# Sensor_Suite.net
KiCad netlist of a schematic drawn in Altium Designer
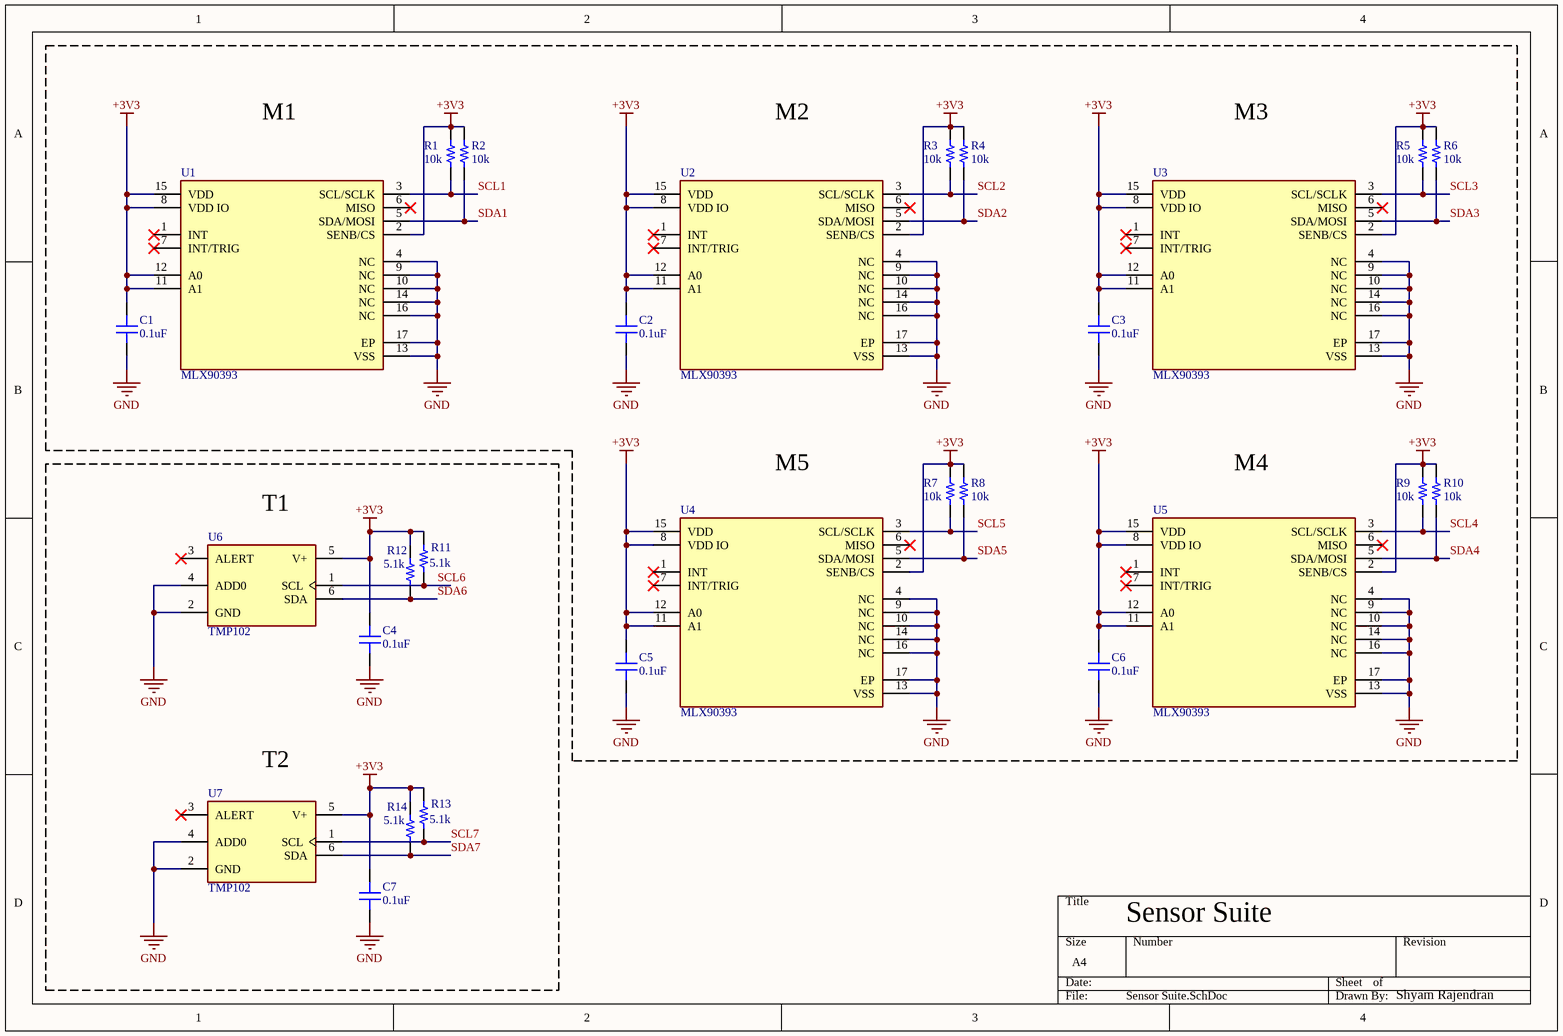
[diagram p0: Sensor Suite.SchDoc]

(export (version "E")
  (design (tool "Eeschema 10.0.6"))
  (components
    (comp (ref "C1")
      (value "10uF")
      (footprint "CAP 0603_1608")
      (description "0603")
      (fields
        (field (name "PART NUMBER") "GCJ188C70J335KE02D")
        (field (name "CAPACITANCE") "0.1uF")
        (field (name "MANUFACTURER") "Murata Electronics")
      )
      (libsource (lib "Celestial Altium Library - altium_library") (part "Capacitor"))
    )
    (comp (ref "C2")
      (value "10uF")
      (footprint "CAP 0603_1608")
      (description "0603")
      (fields
        (field (name "PART NUMBER") "GCJ188C70J335KE02D")
        (field (name "CAPACITANCE") "0.1uF")
        (field (name "MANUFACTURER") "Murata Electronics")
      )
      (libsource (lib "Celestial Altium Library - altium_library") (part "Capacitor"))
    )
    (comp (ref "C3")
      (value "10uF")
      (footprint "CAP 0603_1608")
      (description "0603")
      (fields
        (field (name "PART NUMBER") "GCJ188C70J335KE02D")
        (field (name "CAPACITANCE") "0.1uF")
        (field (name "MANUFACTURER") "Murata Electronics")
      )
      (libsource (lib "Celestial Altium Library - altium_library") (part "Capacitor"))
    )
    (comp (ref "C4")
      (value "10uF")
      (footprint "CAP 0603_1608")
      (description "0603")
      (fields
        (field (name "PART NUMBER") "GCJ188C70J335KE02D")
        (field (name "CAPACITANCE") "0.1uF")
        (field (name "MANUFACTURER") "Murata Electronics")
      )
      (libsource (lib "Celestial Altium Library - altium_library") (part "Capacitor"))
    )
    (comp (ref "C5")
      (value "10uF")
      (footprint "CAP 0603_1608")
      (description "0603")
      (fields
        (field (name "PART NUMBER") "GCJ188C70J335KE02D")
        (field (name "CAPACITANCE") "0.1uF")
        (field (name "MANUFACTURER") "Murata Electronics")
      )
      (libsource (lib "Celestial Altium Library - altium_library") (part "Capacitor"))
    )
    (comp (ref "C6")
      (value "10uF")
      (footprint "CAP 0603_1608")
      (description "0603")
      (fields
        (field (name "PART NUMBER") "GCJ188C70J335KE02D")
        (field (name "CAPACITANCE") "0.1uF")
        (field (name "MANUFACTURER") "Murata Electronics")
      )
      (libsource (lib "Celestial Altium Library - altium_library") (part "Capacitor"))
    )
    (comp (ref "C7")
      (value "10uF")
      (footprint "CAP 0603_1608")
      (description "0603")
      (fields
        (field (name "PART NUMBER") "GCJ188C70J335KE02D")
        (field (name "CAPACITANCE") "0.1uF")
        (field (name "MANUFACTURER") "Murata Electronics")
      )
      (libsource (lib "Celestial Altium Library - altium_library") (part "Capacitor"))
    )
    (comp (ref "R1")
      (value "10k")
      (footprint "RES 0603_1608")
      (description "RES 10K OHM 0.1% 1/16W 0603")
      (fields
        (field (name "PART NUMBER") "RNCS0603BKE10K0")
        (field (name "MANUFACTURER") "Stackpole Electronics Inc")
      )
      (libsource (lib "Celestial Altium Library - altium_library") (part "Resistor"))
    )
    (comp (ref "R2")
      (value "10k")
      (footprint "RES 0603_1608")
      (description "RES 10K OHM 0.1% 1/16W 0603")
      (fields
        (field (name "PART NUMBER") "RNCS0603BKE10K0")
        (field (name "MANUFACTURER") "Stackpole Electronics Inc")
      )
      (libsource (lib "Celestial Altium Library - altium_library") (part "Resistor"))
    )
    (comp (ref "R3")
      (value "10k")
      (footprint "RES 0603_1608")
      (description "RES 10K OHM 0.1% 1/16W 0603")
      (fields
        (field (name "PART NUMBER") "RNCS0603BKE10K0")
        (field (name "MANUFACTURER") "Stackpole Electronics Inc")
      )
      (libsource (lib "Celestial Altium Library - altium_library") (part "Resistor"))
    )
    (comp (ref "R4")
      (value "10k")
      (footprint "RES 0603_1608")
      (description "RES 10K OHM 0.1% 1/16W 0603")
      (fields
        (field (name "PART NUMBER") "RNCS0603BKE10K0")
        (field (name "MANUFACTURER") "Stackpole Electronics Inc")
      )
      (libsource (lib "Celestial Altium Library - altium_library") (part "Resistor"))
    )
    (comp (ref "R5")
      (value "10k")
      (footprint "RES 0603_1608")
      (description "RES 10K OHM 0.1% 1/16W 0603")
      (fields
        (field (name "PART NUMBER") "RNCS0603BKE10K0")
        (field (name "MANUFACTURER") "Stackpole Electronics Inc")
      )
      (libsource (lib "Celestial Altium Library - altium_library") (part "Resistor"))
    )
    (comp (ref "R6")
      (value "10k")
      (footprint "RES 0603_1608")
      (description "RES 10K OHM 0.1% 1/16W 0603")
      (fields
        (field (name "PART NUMBER") "RNCS0603BKE10K0")
        (field (name "MANUFACTURER") "Stackpole Electronics Inc")
      )
      (libsource (lib "Celestial Altium Library - altium_library") (part "Resistor"))
    )
    (comp (ref "R7")
      (value "10k")
      (footprint "RES 0603_1608")
      (description "RES 10K OHM 0.1% 1/16W 0603")
      (fields
        (field (name "PART NUMBER") "RNCS0603BKE10K0")
        (field (name "MANUFACTURER") "Stackpole Electronics Inc")
      )
      (libsource (lib "Celestial Altium Library - altium_library") (part "Resistor"))
    )
    (comp (ref "R8")
      (value "10k")
      (footprint "RES 0603_1608")
      (description "RES 10K OHM 0.1% 1/16W 0603")
      (fields
        (field (name "PART NUMBER") "RNCS0603BKE10K0")
        (field (name "MANUFACTURER") "Stackpole Electronics Inc")
      )
      (libsource (lib "Celestial Altium Library - altium_library") (part "Resistor"))
    )
    (comp (ref "R9")
      (value "10k")
      (footprint "RES 0603_1608")
      (description "RES 10K OHM 0.1% 1/16W 0603")
      (fields
        (field (name "PART NUMBER") "RNCS0603BKE10K0")
        (field (name "MANUFACTURER") "Stackpole Electronics Inc")
      )
      (libsource (lib "Celestial Altium Library - altium_library") (part "Resistor"))
    )
    (comp (ref "R10")
      (value "10k")
      (footprint "RES 0603_1608")
      (description "RES 10K OHM 0.1% 1/16W 0603")
      (fields
        (field (name "PART NUMBER") "RNCS0603BKE10K0")
        (field (name "MANUFACTURER") "Stackpole Electronics Inc")
      )
      (libsource (lib "Celestial Altium Library - altium_library") (part "Resistor"))
    )
    (comp (ref "R11")
      (value "5.1k")
      (footprint "RES 0603_1608")
      (description "0603")
      (fields
        (field (name "PART NUMBER") "RNCS0603BKE10K0")
        (field (name "MANUFACTURER") "Stackpole Electronics Inc")
      )
      (libsource (lib "Celestial Altium Library - altium_library") (part "Resistor"))
    )
    (comp (ref "R12")
      (value "5.1k")
      (footprint "RES 0603_1608")
      (description "0603")
      (fields
        (field (name "PART NUMBER") "RNCS0603BKE10K0")
        (field (name "MANUFACTURER") "Stackpole Electronics Inc")
      )
      (libsource (lib "Celestial Altium Library - altium_library") (part "Resistor"))
    )
    (comp (ref "R13")
      (value "5.1k")
      (footprint "RES 0603_1608")
      (description "0603")
      (fields
        (field (name "PART NUMBER") "RNCS0603BKE10K0")
        (field (name "MANUFACTURER") "Stackpole Electronics Inc")
      )
      (libsource (lib "Celestial Altium Library - altium_library") (part "Resistor"))
    )
    (comp (ref "R14")
      (value "5.1k")
      (footprint "RES 0603_1608")
      (description "0603")
      (fields
        (field (name "PART NUMBER") "RNCS0603BKE10K0")
        (field (name "MANUFACTURER") "Stackpole Electronics Inc")
      )
      (libsource (lib "Celestial Altium Library - altium_library") (part "Resistor"))
    )
    (comp (ref "U1")
      (value "MLX90393")
      (footprint "MLX90393")
      (description "Analog Circuit, 1 Func")
      (fields
        (field (name "MANUFACTURER") "Melexis")
        (field (name "MANUFACTURER PART NUMBER") "MLX90393ELW-ABA-011-RE")
      )
      (libsource (lib "Schlib1") (part "MLX90393ELW-ABA-011-RE"))
    )
    (comp (ref "U2")
      (value "MLX90393")
      (footprint "MLX90393")
      (description "Analog Circuit, 1 Func")
      (fields
        (field (name "MANUFACTURER") "Melexis")
        (field (name "MANUFACTURER PART NUMBER") "MLX90393ELW-ABA-011-RE")
      )
      (libsource (lib "Schlib1") (part "MLX90393ELW-ABA-011-RE"))
    )
    (comp (ref "U3")
      (value "MLX90393")
      (footprint "MLX90393")
      (description "Analog Circuit, 1 Func")
      (fields
        (field (name "MANUFACTURER") "Melexis")
        (field (name "MANUFACTURER PART NUMBER") "MLX90393ELW-ABA-011-RE")
      )
      (libsource (lib "Schlib1") (part "MLX90393ELW-ABA-011-RE"))
    )
    (comp (ref "U4")
      (value "MLX90393")
      (footprint "MLX90393")
      (description "Analog Circuit, 1 Func")
      (fields
        (field (name "MANUFACTURER") "Melexis")
        (field (name "MANUFACTURER PART NUMBER") "MLX90393ELW-ABA-011-RE")
      )
      (libsource (lib "Schlib1") (part "MLX90393ELW-ABA-011-RE"))
    )
    (comp (ref "U5")
      (value "MLX90393")
      (footprint "MLX90393")
      (description "Analog Circuit, 1 Func")
      (fields
        (field (name "MANUFACTURER") "Melexis")
        (field (name "MANUFACTURER PART NUMBER") "MLX90393ELW-ABA-011-RE")
      )
      (libsource (lib "Schlib1") (part "MLX90393ELW-ABA-011-RE"))
    )
    (comp (ref "U6")
      (value "TMP102")
      (footprint "TMP102")
      (description "SENSOR DIGITAL -40C-125C SOT563")
      (libsource (lib "Schlib1") (part "TMP102"))
    )
    (comp (ref "U7")
      (value "TMP102")
      (footprint "TMP102")
      (description "SENSOR DIGITAL -40C-125C SOT563")
      (libsource (lib "Schlib1") (part "TMP102"))
    )
  )
  (nets
    (net (code "1") (name "+3V3") (class "Default")
      (node (ref "C1") (pin "2") (pinfunction "2_2") (pintype "passive"))
      (node (ref "C2") (pin "2") (pinfunction "2_2") (pintype "passive"))
      (node (ref "C3") (pin "2") (pinfunction "2_2") (pintype "passive"))
      (node (ref "C4") (pin "2") (pinfunction "2_2") (pintype "passive"))
      (node (ref "C5") (pin "2") (pinfunction "2_2") (pintype "passive"))
      (node (ref "C6") (pin "2") (pinfunction "2_2") (pintype "passive"))
      (node (ref "C7") (pin "2") (pinfunction "2_2") (pintype "passive"))
      (node (ref "R1") (pin "2") (pinfunction "2_2") (pintype "passive"))
      (node (ref "R10") (pin "2") (pinfunction "2_2") (pintype "passive"))
      (node (ref "R11") (pin "1") (pinfunction "1_1") (pintype "passive"))
      (node (ref "R12") (pin "1") (pinfunction "1_1") (pintype "passive"))
      (node (ref "R13") (pin "1") (pinfunction "1_1") (pintype "passive"))
      (node (ref "R14") (pin "1") (pinfunction "1_1") (pintype "passive"))
      (node (ref "R2") (pin "2") (pinfunction "2_2") (pintype "passive"))
      (node (ref "R3") (pin "2") (pinfunction "2_2") (pintype "passive"))
      (node (ref "R4") (pin "2") (pinfunction "2_2") (pintype "passive"))
      (node (ref "R5") (pin "2") (pinfunction "2_2") (pintype "passive"))
      (node (ref "R6") (pin "2") (pinfunction "2_2") (pintype "passive"))
      (node (ref "R7") (pin "2") (pinfunction "2_2") (pintype "passive"))
      (node (ref "R8") (pin "2") (pinfunction "2_2") (pintype "passive"))
      (node (ref "R9") (pin "2") (pinfunction "2_2") (pintype "passive"))
      (node (ref "U1") (pin "11") (pinfunction "A1_11") (pintype "passive"))
      (node (ref "U1") (pin "12") (pinfunction "A0_12") (pintype "passive"))
      (node (ref "U1") (pin "15") (pinfunction "VDD_15") (pintype "passive"))
      (node (ref "U1") (pin "2") (pinfunction "SENB/CS_2") (pintype "passive"))
      (node (ref "U1") (pin "8") (pinfunction "VDD_IO_8") (pintype "passive"))
      (node (ref "U2") (pin "11") (pinfunction "A1_11") (pintype "passive"))
      (node (ref "U2") (pin "12") (pinfunction "A0_12") (pintype "passive"))
      (node (ref "U2") (pin "15") (pinfunction "VDD_15") (pintype "passive"))
      (node (ref "U2") (pin "2") (pinfunction "SENB/CS_2") (pintype "passive"))
      (node (ref "U2") (pin "8") (pinfunction "VDD_IO_8") (pintype "passive"))
      (node (ref "U3") (pin "11") (pinfunction "A1_11") (pintype "passive"))
      (node (ref "U3") (pin "12") (pinfunction "A0_12") (pintype "passive"))
      (node (ref "U3") (pin "15") (pinfunction "VDD_15") (pintype "passive"))
      (node (ref "U3") (pin "2") (pinfunction "SENB/CS_2") (pintype "passive"))
      (node (ref "U3") (pin "8") (pinfunction "VDD_IO_8") (pintype "passive"))
      (node (ref "U4") (pin "11") (pinfunction "A1_11") (pintype "passive"))
      (node (ref "U4") (pin "12") (pinfunction "A0_12") (pintype "passive"))
      (node (ref "U4") (pin "15") (pinfunction "VDD_15") (pintype "passive"))
      (node (ref "U4") (pin "2") (pinfunction "SENB/CS_2") (pintype "passive"))
      (node (ref "U4") (pin "8") (pinfunction "VDD_IO_8") (pintype "passive"))
      (node (ref "U5") (pin "11") (pinfunction "A1_11") (pintype "passive"))
      (node (ref "U5") (pin "12") (pinfunction "A0_12") (pintype "passive"))
      (node (ref "U5") (pin "15") (pinfunction "VDD_15") (pintype "passive"))
      (node (ref "U5") (pin "2") (pinfunction "SENB/CS_2") (pintype "passive"))
      (node (ref "U5") (pin "8") (pinfunction "VDD_IO_8") (pintype "passive"))
      (node (ref "U6") (pin "5") (pinfunction "V+_5") (pintype "passive"))
      (node (ref "U7") (pin "5") (pinfunction "V+_5") (pintype "passive"))
    )
    (net (code "2") (name "/SCL1") (class "Default")
      (node (ref "R1") (pin "1") (pinfunction "1_1") (pintype "passive"))
      (node (ref "U1") (pin "3") (pinfunction "SCL/SCLK_3") (pintype "passive"))
    )
    (net (code "3") (name "/SCL2") (class "Default")
      (node (ref "R3") (pin "1") (pinfunction "1_1") (pintype "passive"))
      (node (ref "U2") (pin "3") (pinfunction "SCL/SCLK_3") (pintype "passive"))
    )
    (net (code "4") (name "/SCL3") (class "Default")
      (node (ref "R5") (pin "1") (pinfunction "1_1") (pintype "passive"))
      (node (ref "U3") (pin "3") (pinfunction "SCL/SCLK_3") (pintype "passive"))
    )
    (net (code "5") (name "/SCL4") (class "Default")
      (node (ref "R9") (pin "1") (pinfunction "1_1") (pintype "passive"))
      (node (ref "U5") (pin "3") (pinfunction "SCL/SCLK_3") (pintype "passive"))
    )
    (net (code "6") (name "/SCL5") (class "Default")
      (node (ref "R7") (pin "1") (pinfunction "1_1") (pintype "passive"))
      (node (ref "U4") (pin "3") (pinfunction "SCL/SCLK_3") (pintype "passive"))
    )
    (net (code "7") (name "/SCL6") (class "Default")
      (node (ref "R11") (pin "2") (pinfunction "2_2") (pintype "passive"))
      (node (ref "U6") (pin "1") (pinfunction "SCL_1") (pintype "passive"))
    )
    (net (code "8") (name "/SCL7") (class "Default")
      (node (ref "R13") (pin "2") (pinfunction "2_2") (pintype "passive"))
      (node (ref "U7") (pin "1") (pinfunction "SCL_1") (pintype "passive"))
    )
    (net (code "9") (name "/SDA1") (class "Default")
      (node (ref "R2") (pin "1") (pinfunction "1_1") (pintype "passive"))
      (node (ref "U1") (pin "5") (pinfunction "SDA/MOSI_5") (pintype "passive"))
    )
    (net (code "10") (name "/SDA2") (class "Default")
      (node (ref "R4") (pin "1") (pinfunction "1_1") (pintype "passive"))
      (node (ref "U2") (pin "5") (pinfunction "SDA/MOSI_5") (pintype "passive"))
    )
    (net (code "11") (name "/SDA3") (class "Default")
      (node (ref "R6") (pin "1") (pinfunction "1_1") (pintype "passive"))
      (node (ref "U3") (pin "5") (pinfunction "SDA/MOSI_5") (pintype "passive"))
    )
    (net (code "12") (name "/SDA4") (class "Default")
      (node (ref "R10") (pin "1") (pinfunction "1_1") (pintype "passive"))
      (node (ref "U5") (pin "5") (pinfunction "SDA/MOSI_5") (pintype "passive"))
    )
    (net (code "13") (name "/SDA5") (class "Default")
      (node (ref "R8") (pin "1") (pinfunction "1_1") (pintype "passive"))
      (node (ref "U4") (pin "5") (pinfunction "SDA/MOSI_5") (pintype "passive"))
    )
    (net (code "14") (name "/SDA6") (class "Default")
      (node (ref "R12") (pin "2") (pinfunction "2_2") (pintype "passive"))
      (node (ref "U6") (pin "6") (pinfunction "SDA_6") (pintype "passive"))
    )
    (net (code "15") (name "/SDA7") (class "Default")
      (node (ref "R14") (pin "2") (pinfunction "2_2") (pintype "passive"))
      (node (ref "U7") (pin "6") (pinfunction "SDA_6") (pintype "passive"))
    )
    (net (code "16") (name "GND") (class "Default")
      (node (ref "C1") (pin "1") (pinfunction "1_1") (pintype "passive"))
      (node (ref "C2") (pin "1") (pinfunction "1_1") (pintype "passive"))
      (node (ref "C3") (pin "1") (pinfunction "1_1") (pintype "passive"))
      (node (ref "C4") (pin "1") (pinfunction "1_1") (pintype "passive"))
      (node (ref "C5") (pin "1") (pinfunction "1_1") (pintype "passive"))
      (node (ref "C6") (pin "1") (pinfunction "1_1") (pintype "passive"))
      (node (ref "C7") (pin "1") (pinfunction "1_1") (pintype "passive"))
      (node (ref "U1") (pin "10") (pinfunction "NC_10") (pintype "passive"))
      (node (ref "U1") (pin "13") (pinfunction "VSS_13") (pintype "passive"))
      (node (ref "U1") (pin "14") (pinfunction "NC_14") (pintype "passive"))
      (node (ref "U1") (pin "16") (pinfunction "NC_16") (pintype "passive"))
      (node (ref "U1") (pin "17") (pinfunction "EP_17") (pintype "passive"))
      (node (ref "U1") (pin "4") (pinfunction "NC_4") (pintype "passive"))
      (node (ref "U1") (pin "9") (pinfunction "NC_9") (pintype "passive"))
      (node (ref "U2") (pin "10") (pinfunction "NC_10") (pintype "passive"))
      (node (ref "U2") (pin "13") (pinfunction "VSS_13") (pintype "passive"))
      (node (ref "U2") (pin "14") (pinfunction "NC_14") (pintype "passive"))
      (node (ref "U2") (pin "16") (pinfunction "NC_16") (pintype "passive"))
      (node (ref "U2") (pin "17") (pinfunction "EP_17") (pintype "passive"))
      (node (ref "U2") (pin "4") (pinfunction "NC_4") (pintype "passive"))
      (node (ref "U2") (pin "9") (pinfunction "NC_9") (pintype "passive"))
      (node (ref "U3") (pin "10") (pinfunction "NC_10") (pintype "passive"))
      (node (ref "U3") (pin "13") (pinfunction "VSS_13") (pintype "passive"))
      (node (ref "U3") (pin "14") (pinfunction "NC_14") (pintype "passive"))
      (node (ref "U3") (pin "16") (pinfunction "NC_16") (pintype "passive"))
      (node (ref "U3") (pin "17") (pinfunction "EP_17") (pintype "passive"))
      (node (ref "U3") (pin "4") (pinfunction "NC_4") (pintype "passive"))
      (node (ref "U3") (pin "9") (pinfunction "NC_9") (pintype "passive"))
      (node (ref "U4") (pin "10") (pinfunction "NC_10") (pintype "passive"))
      (node (ref "U4") (pin "13") (pinfunction "VSS_13") (pintype "passive"))
      (node (ref "U4") (pin "14") (pinfunction "NC_14") (pintype "passive"))
      (node (ref "U4") (pin "16") (pinfunction "NC_16") (pintype "passive"))
      (node (ref "U4") (pin "17") (pinfunction "EP_17") (pintype "passive"))
      (node (ref "U4") (pin "4") (pinfunction "NC_4") (pintype "passive"))
      (node (ref "U4") (pin "9") (pinfunction "NC_9") (pintype "passive"))
      (node (ref "U5") (pin "10") (pinfunction "NC_10") (pintype "passive"))
      (node (ref "U5") (pin "13") (pinfunction "VSS_13") (pintype "passive"))
      (node (ref "U5") (pin "14") (pinfunction "NC_14") (pintype "passive"))
      (node (ref "U5") (pin "16") (pinfunction "NC_16") (pintype "passive"))
      (node (ref "U5") (pin "17") (pinfunction "EP_17") (pintype "passive"))
      (node (ref "U5") (pin "4") (pinfunction "NC_4") (pintype "passive"))
      (node (ref "U5") (pin "9") (pinfunction "NC_9") (pintype "passive"))
      (node (ref "U6") (pin "2") (pinfunction "GND_2") (pintype "passive"))
      (node (ref "U6") (pin "4") (pinfunction "ADD0_4") (pintype "passive"))
      (node (ref "U7") (pin "2") (pinfunction "GND_2") (pintype "passive"))
      (node (ref "U7") (pin "4") (pinfunction "ADD0_4") (pintype "passive"))
    )
    (net (code "17") (name "unconnected-(U1-INT-Pad1)") (class "Default")
      (node (ref "U1") (pin "1") (pinfunction "INT_1") (pintype "passive+no_connect"))
    )
    (net (code "18") (name "unconnected-(U1-INT{slash}TRIG-Pad7)") (class "Default")
      (node (ref "U1") (pin "7") (pinfunction "INT/TRIG_7") (pintype "passive+no_connect"))
    )
    (net (code "19") (name "unconnected-(U1-MISO-Pad6)") (class "Default")
      (node (ref "U1") (pin "6") (pinfunction "MISO_6") (pintype "passive+no_connect"))
    )
    (net (code "20") (name "unconnected-(U2-INT-Pad1)") (class "Default")
      (node (ref "U2") (pin "1") (pinfunction "INT_1") (pintype "passive+no_connect"))
    )
    (net (code "21") (name "unconnected-(U2-INT{slash}TRIG-Pad7)") (class "Default")
      (node (ref "U2") (pin "7") (pinfunction "INT/TRIG_7") (pintype "passive+no_connect"))
    )
    (net (code "22") (name "unconnected-(U2-MISO-Pad6)") (class "Default")
      (node (ref "U2") (pin "6") (pinfunction "MISO_6") (pintype "passive+no_connect"))
    )
    (net (code "23") (name "unconnected-(U3-INT-Pad1)") (class "Default")
      (node (ref "U3") (pin "1") (pinfunction "INT_1") (pintype "passive+no_connect"))
    )
    (net (code "24") (name "unconnected-(U3-INT{slash}TRIG-Pad7)") (class "Default")
      (node (ref "U3") (pin "7") (pinfunction "INT/TRIG_7") (pintype "passive+no_connect"))
    )
    (net (code "25") (name "unconnected-(U3-MISO-Pad6)") (class "Default")
      (node (ref "U3") (pin "6") (pinfunction "MISO_6") (pintype "passive+no_connect"))
    )
    (net (code "26") (name "unconnected-(U4-INT-Pad1)") (class "Default")
      (node (ref "U4") (pin "1") (pinfunction "INT_1") (pintype "passive+no_connect"))
    )
    (net (code "27") (name "unconnected-(U4-INT{slash}TRIG-Pad7)") (class "Default")
      (node (ref "U4") (pin "7") (pinfunction "INT/TRIG_7") (pintype "passive+no_connect"))
    )
    (net (code "28") (name "unconnected-(U4-MISO-Pad6)") (class "Default")
      (node (ref "U4") (pin "6") (pinfunction "MISO_6") (pintype "passive+no_connect"))
    )
    (net (code "29") (name "unconnected-(U5-INT-Pad1)") (class "Default")
      (node (ref "U5") (pin "1") (pinfunction "INT_1") (pintype "passive+no_connect"))
    )
    (net (code "30") (name "unconnected-(U5-INT{slash}TRIG-Pad7)") (class "Default")
      (node (ref "U5") (pin "7") (pinfunction "INT/TRIG_7") (pintype "passive+no_connect"))
    )
    (net (code "31") (name "unconnected-(U5-MISO-Pad6)") (class "Default")
      (node (ref "U5") (pin "6") (pinfunction "MISO_6") (pintype "passive+no_connect"))
    )
    (net (code "32") (name "unconnected-(U6-ALERT-Pad3)") (class "Default")
      (node (ref "U6") (pin "3") (pinfunction "ALERT_3") (pintype "passive+no_connect"))
    )
    (net (code "33") (name "unconnected-(U7-ALERT-Pad3)") (class "Default")
      (node (ref "U7") (pin "3") (pinfunction "ALERT_3") (pintype "passive+no_connect"))
    )
  )
)
